# Ikea_Environmental_Sensor-Module.net
KiCad netlist of a schematic drawn in Altium Designer
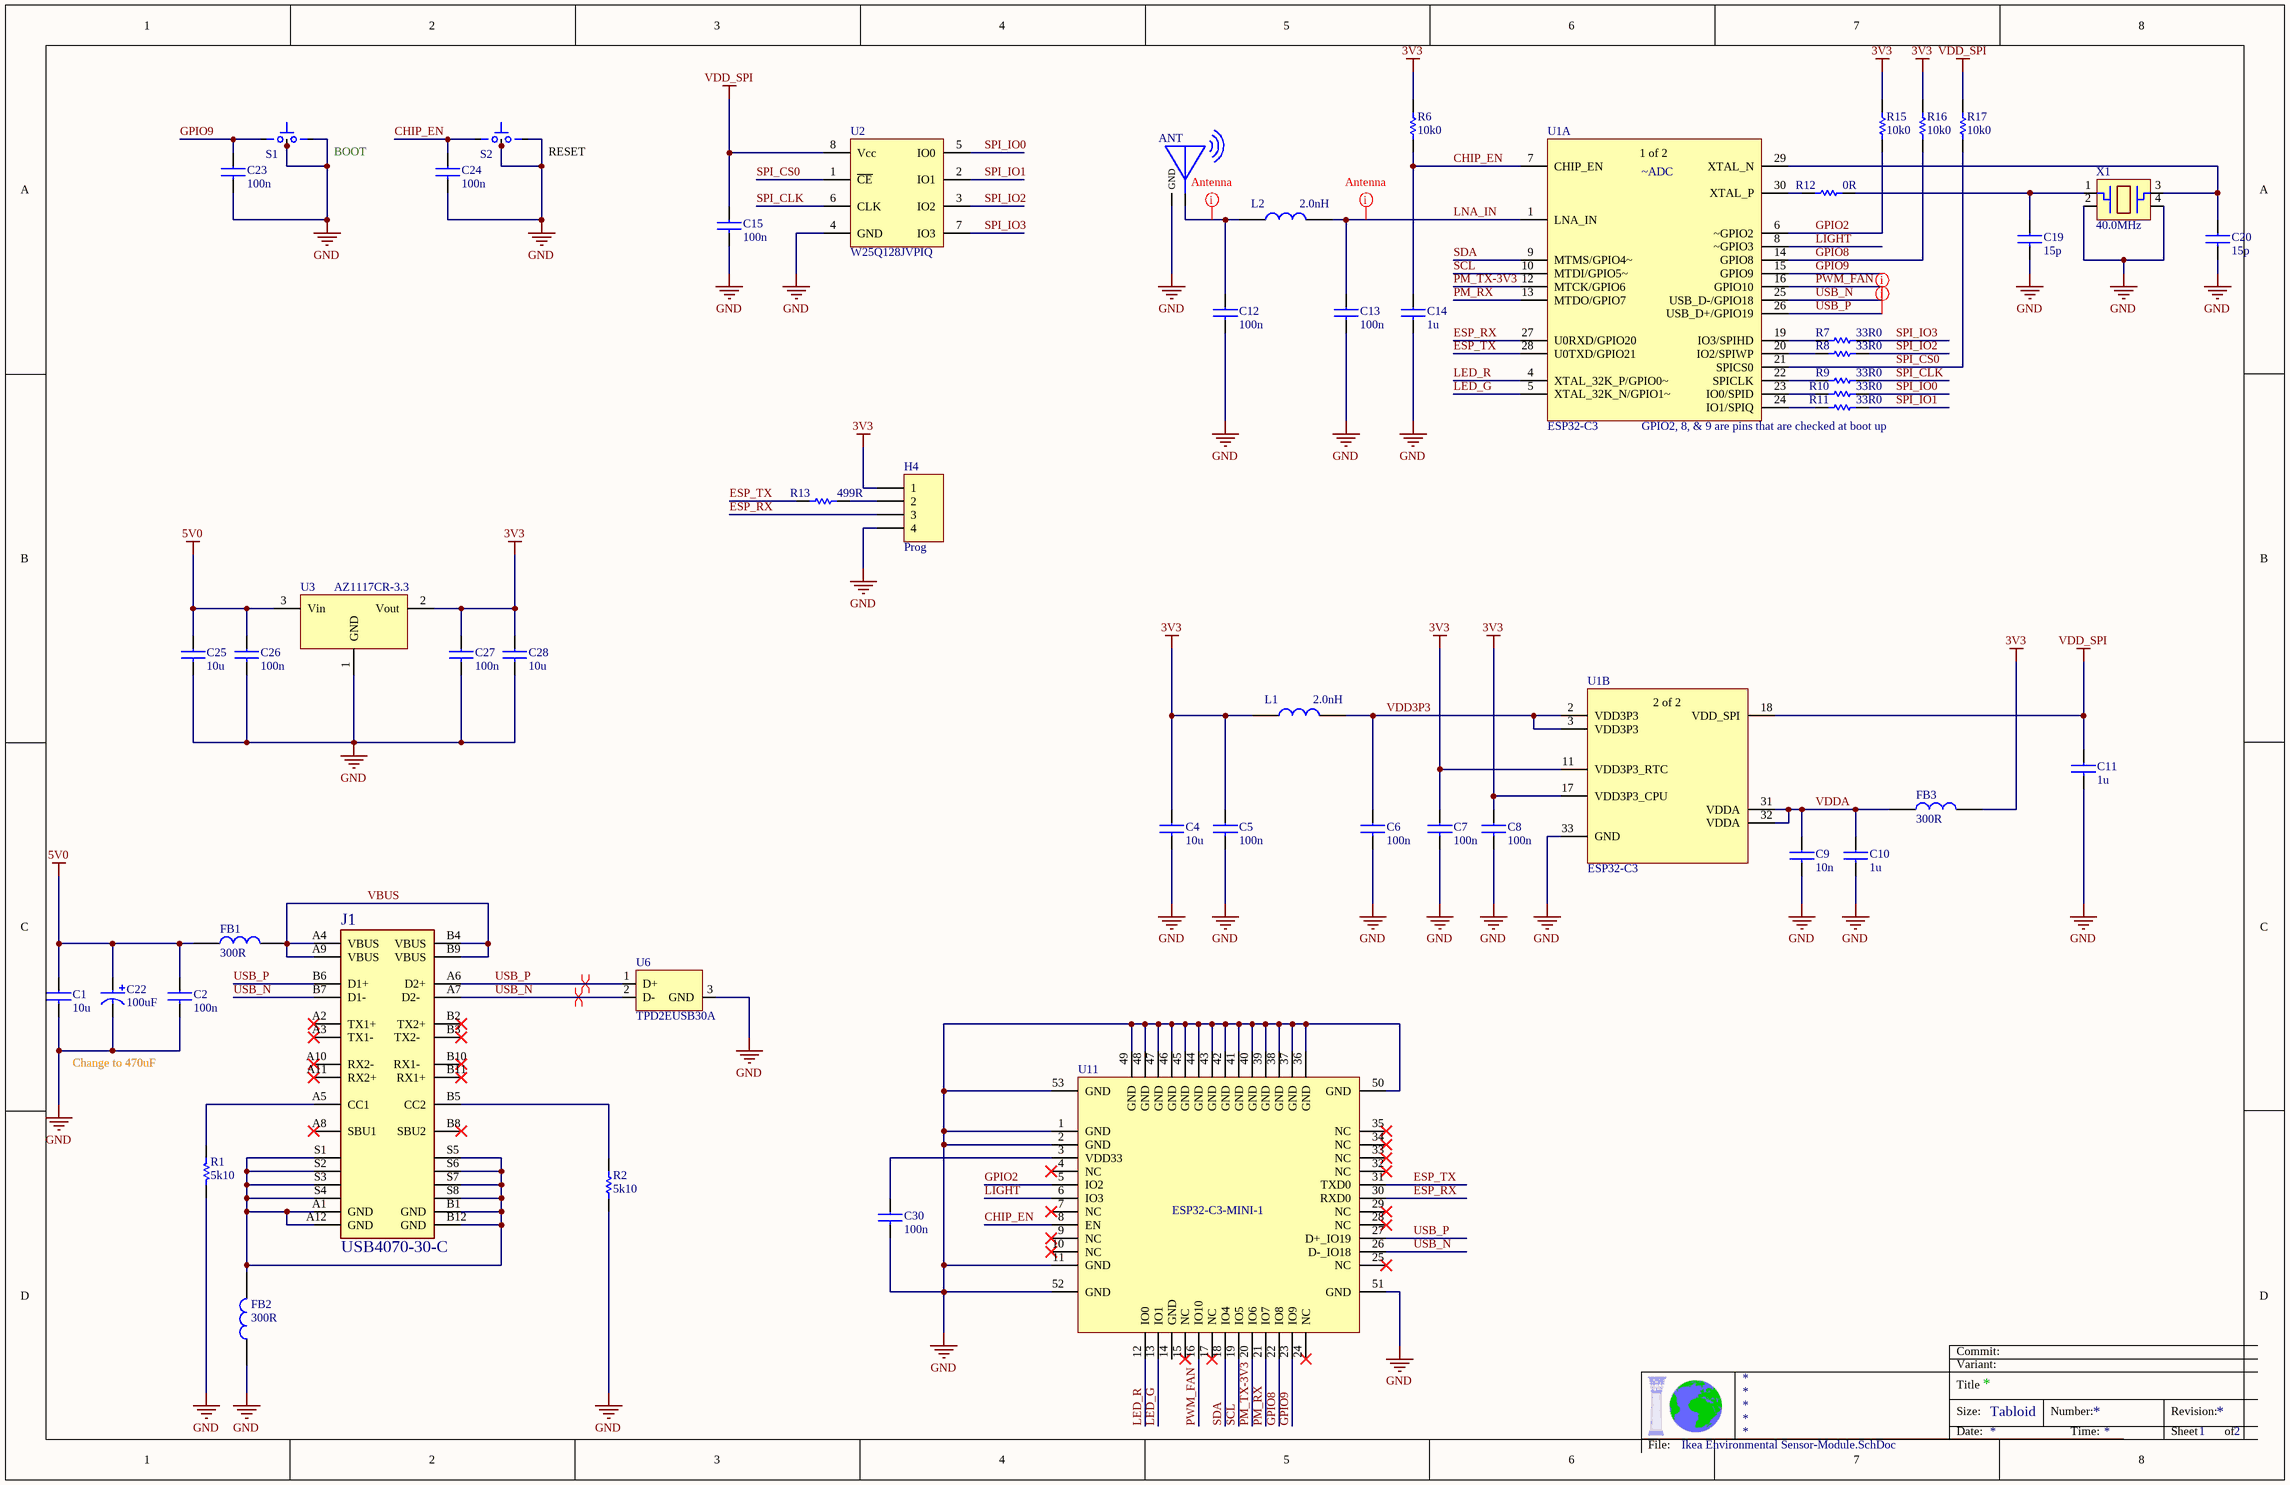
[diagram p0: Ikea Environmental Sensor-Module.SchDoc]

(export (version "E")
  (design (tool "Eeschema 10.0.6"))
  (components
    (comp (ref "ANT")
      (value "PCB Antenna")
      (footprint "MINI-ANT-TYPED-H - Flipped")
      (description "Antenna MIFA 2.4Gig")
      (fields (field (name "MANUFACTURER") "Rainsun") (field (name "LCSC_PART_NUMBER") "C99665"))
      (libsource (lib "GLIB") (part "Antenna_PCB_MIFA"))
    )
    (comp (ref "C1")
      (value "10u")
      (footprint "0603X90")
      (description "Cap, Chip, 10uF, 10V, ± 15%, X5R, 0603")
      (fields (field (name "MANUFACTURER") "NIC") (field (name "JLCPCB_PART_#") "C96446"))
      (libsource (lib "GLIB") (part "C_10u_10V_10_0603_NIC"))
    )
    (comp (ref "C2")
      (value "100n")
      (footprint "C_0402_N")
      (description "Cap, Chip, 100nF, 16V, +/-10%, X7R, 0402")
      (fields (field (name "MANUFACTURER") "NIC") (field (name "JLCPCB_PART_#") "C307331"))
      (libsource (lib "GLIB") (part "C_100n_16V_10_0402_NIC"))
    )
    (comp (ref "C4")
      (value "10u")
      (footprint "0603X90")
      (description "Cap, Chip, 10uF, 10V, ± 15%, X5R, 0603")
      (fields (field (name "MANUFACTURER") "NIC"))
      (libsource (lib "GLIB") (part "C_10u_10V_10_0603_NIC"))
    )
    (comp (ref "C5")
      (value "100n")
      (footprint "C_0402_N")
      (description "Cap, Chip, 100nF, 16V, +/-10%, X7R, 0402")
      (fields (field (name "MANUFACTURER") "NIC"))
      (libsource (lib "GLIB") (part "C_100n_16V_10_0402_NIC"))
    )
    (comp (ref "C6")
      (value "100n")
      (footprint "C_0402_N")
      (description "Cap, Chip, 100nF, 16V, +/-10%, X7R, 0402")
      (fields (field (name "MANUFACTURER") "NIC"))
      (libsource (lib "GLIB") (part "C_100n_16V_10_0402_NIC"))
    )
    (comp (ref "C7")
      (value "100n")
      (footprint "C_0402_N")
      (description "Cap, Chip, 100nF, 16V, +/-10%, X7R, 0402")
      (fields (field (name "MANUFACTURER") "NIC"))
      (libsource (lib "GLIB") (part "C_100n_16V_10_0402_NIC"))
    )
    (comp (ref "C8")
      (value "100n")
      (footprint "C_0402_N")
      (description "Cap, Chip, 100nF, 16V, +/-10%, X7R, 0402")
      (fields (field (name "MANUFACTURER") "NIC"))
      (libsource (lib "GLIB") (part "C_100n_16V_10_0402_NIC"))
    )
    (comp (ref "C9")
      (value "10n")
      (footprint "C_0402_N")
      (description "Cap, Chip, 0.01uF, 25V, 20%, X7R, 0402")
      (fields (field (name "MANUFACTURER") "NIC"))
      (libsource (lib "GLIB") (part "C_10n_25V_20_0402_NIC"))
    )
    (comp (ref "C10")
      (value "1u")
      (footprint "C_0402_N")
      (description "Cap, Chip, 1uF, 10V, 10%, X5R, 0402")
      (fields (field (name "MANUFACTURER") "NIC"))
      (libsource (lib "GLIB") (part "C_1u_10V_10_0402_NIC"))
    )
    (comp (ref "C11")
      (value "1u")
      (footprint "C_0402_N")
      (description "Cap, Chip, 1uF, 10V, 10%, X5R, 0402")
      (fields (field (name "MANUFACTURER") "NIC"))
      (libsource (lib "GLIB") (part "C_1u_10V_10_0402_NIC"))
    )
    (comp (ref "C12")
      (value "100n")
      (footprint "C_0201")
      (description "Cap, Chip, 100nF, 25V, +/-10%, X5R, 0201")
      (fields (field (name "MANUFACTURER") "Murata"))
      (libsource (lib "GLIB") (part "C_100n_25V_10_0201_Murata"))
    )
    (comp (ref "C13")
      (value "100n")
      (footprint "C_0201")
      (description "Cap, Chip, 100nF, 25V, +/-10%, X5R, 0201")
      (fields (field (name "MANUFACTURER") "Murata"))
      (libsource (lib "GLIB") (part "C_100n_25V_10_0201_Murata"))
    )
    (comp (ref "C14")
      (value "1u")
      (footprint "C_0402_N")
      (description "Cap, Chip, 1uF, 10V, 10%, X5R, 0402")
      (fields (field (name "MANUFACTURER") "NIC"))
      (libsource (lib "GLIB") (part "C_1u_10V_10_0402_NIC"))
    )
    (comp (ref "C15")
      (value "100n")
      (footprint "C_0402_N")
      (description "Cap, Chip, 100nF, 16V, +/-10%, X7R, 0402")
      (fields (field (name "MANUFACTURER") "NIC"))
      (libsource (lib "GLIB") (part "C_100n_16V_10_0402_NIC"))
    )
    (comp (ref "C19")
      (value "15p")
      (footprint "C_0402_N")
      (description "Cap, Chip, 15pF, 25V, 10%, NPO 0402")
      (fields (field (name "MANUFACTURER") "NIC"))
      (libsource (lib "GLIB") (part "C_15p_25V_10_0402_NIC"))
    )
    (comp (ref "C20")
      (value "15p")
      (footprint "C_0402_N")
      (description "Cap, Chip, 15pF, 25V, 10%, NPO 0402")
      (fields (field (name "MANUFACTURER") "NIC"))
      (libsource (lib "GLIB") (part "C_15p_25V_10_0402_NIC"))
    )
    (comp (ref "C22")
      (value "100uF")
      (footprint "CAP_6.6x6.6")
      (description "Cap AlEl, 100uF, 35V, 20%, 6.6mm dia.")
      (fields (field (name "MANUFACTURER") "Panasonic") (field (name "Comment") "100uF, 35V"))
      (libsource (lib "GLIB") (part "C_100uF_35V_20_6.6mm_Panasonic"))
    )
    (comp (ref "C23")
      (value "100n")
      (footprint "C_0402_N")
      (description "Cap, Chip, 100nF, 16V, +/-10%, X7R, 0402")
      (fields (field (name "MANUFACTURER") "NIC"))
      (libsource (lib "GLIB") (part "C_100n_16V_10_0402_NIC"))
    )
    (comp (ref "C24")
      (value "100n")
      (footprint "C_0402_N")
      (description "Cap, Chip, 100nF, 16V, +/-10%, X7R, 0402")
      (fields (field (name "MANUFACTURER") "NIC"))
      (libsource (lib "GLIB") (part "C_100n_16V_10_0402_NIC"))
    )
    (comp (ref "C25")
      (value "10u")
      (footprint "0603X90")
      (description "Cap, Chip, 10uF, 10V, ± 15%, X5R, 0603")
      (fields (field (name "MANUFACTURER") "NIC"))
      (libsource (lib "GLIB") (part "C_10u_10V_10_0603_NIC"))
    )
    (comp (ref "C26")
      (value "100n")
      (footprint "C_0402_N")
      (description "Cap, Chip, 100nF, 16V, +/-10%, X7R, 0402")
      (fields (field (name "MANUFACTURER") "NIC"))
      (libsource (lib "GLIB") (part "C_100n_16V_10_0402_NIC"))
    )
    (comp (ref "C27")
      (value "100n")
      (footprint "C_0402_N")
      (description "Cap, Chip, 100nF, 16V, +/-10%, X7R, 0402")
      (fields (field (name "MANUFACTURER") "NIC"))
      (libsource (lib "GLIB") (part "C_100n_16V_10_0402_NIC"))
    )
    (comp (ref "C28")
      (value "10u")
      (footprint "0603X90")
      (description "Cap, Chip, 10uF, 10V, ± 15%, X5R, 0603")
      (fields (field (name "MANUFACTURER") "NIC"))
      (libsource (lib "GLIB") (part "C_10u_10V_10_0603_NIC"))
    )
    (comp (ref "C30")
      (value "100n")
      (footprint "C_0402_N")
      (description "Cap, Chip, 100nF, 16V, +/-10%, X7R, 0402")
      (fields (field (name "MANUFACTURER") "NIC"))
      (libsource (lib "GLIB") (part "C_100n_16V_10_0402_NIC"))
    )
    (comp (ref "FB1")
      (value "300R")
      (footprint "FB_0402-NIC")
      (description "Ferrite bead,300 ohm@100MHz,0.15 ohm @DC, 1A, 0402")
      (fields (field (name "MANUFACTURER") "NIC"))
      (libsource (lib "GLIB") (part "FB_300R_0402_NIC"))
    )
    (comp (ref "FB2")
      (value "300R")
      (footprint "FB_0402-NIC")
      (description "Ferrite bead,300 ohm@100MHz,0.15 ohm @DC, 1A, 0402")
      (fields (field (name "MANUFACTURER") "NIC"))
      (libsource (lib "GLIB") (part "FB_300R_0402_NIC"))
    )
    (comp (ref "FB3")
      (value "300R")
      (footprint "FB_0402-NIC")
      (description "Ferrite bead,300 ohm@100MHz,0.15 ohm @DC, 1A, 0402")
      (fields (field (name "MANUFACTURER") "NIC"))
      (libsource (lib "GLIB") (part "FB_300R_0402_NIC"))
    )
    (comp (ref "H4")
      (value "Prog")
      (footprint "HDR1X4")
      (description "Header, 4-Pin")
      (libsource (lib "GLIB") (part "Header 4"))
    )
    (comp (ref "J1")
      (value "USB4070-30-C")
      (footprint "USB_C_GCT_USB4070-30-C_REVC5")
      (description "CONN RCPT USB 3.1 Type C Vertical SMT")
      (fields (field (name "MANUFACTURER") "GCT") (field (name "JLCPCB PART #") "C168703"))
      (libsource (lib "GLIB") (part "J_USB_C_REC_SMT_V"))
    )
    (comp (ref "L1")
      (value "2.0nH")
      (footprint "FB_0402-NIC")
      (description "Inductor 2.0nH, +/-0.3nH, LQG15HS2N0S02D, 0402")
      (fields (field (name "MANUFACTURER") "Murata") (field (name "JLCPCB PART #") "C880712"))
      (libsource (lib "GLIB") (part "L_2nH_LQG15HS2N0S02D_0402"))
    )
    (comp (ref "L2")
      (value "2.0nH")
      (footprint "L_0201")
      (description "Inductor 2.0nH, +/-0.1nH, 600mA, 0201")
      (fields (field (name "MANUFACTURER") "Murata"))
      (libsource (lib "GLIB") (part "L_2nH_LQP03TN2N0B02D_0201"))
    )
    (comp (ref "R1")
      (value "5k10")
      (footprint "R_0402-N")
      (description "Resistor, 5.10 kΩ, 1%, 0.06W, 0402")
      (fields (field (name "MANUFACTURER") "NIC") (field (name "JLCPCB_PART_#") "C25905"))
      (libsource (lib "GLIB") (part "R_5k10_60mW_1_0402_NIC"))
    )
    (comp (ref "R2")
      (value "5k10")
      (footprint "R_0402-N")
      (description "Resistor, 5.10 kΩ, 1%, 0.06W, 0402")
      (fields (field (name "MANUFACTURER") "NIC") (field (name "JLCPCB_PART_#") "C25905"))
      (libsource (lib "GLIB") (part "R_5k10_60mW_1_0402_NIC"))
    )
    (comp (ref "R6")
      (value "10k0")
      (footprint "R_0402-N")
      (description "Resistor, 10.0 kΩ, 1%, 0.06W, 0402")
      (fields (field (name "MANUFACTURER") "NIC"))
      (libsource (lib "GLIB") (part "R_10k0_60mW_1_0402_NIC"))
    )
    (comp (ref "R7")
      (value "33R0")
      (footprint "R_0402-N")
      (description "Resistor, 33.0 Ω, 1%, 0.06W, 0402")
      (fields (field (name "MANUFACTURER") "NIC"))
      (libsource (lib "GLIB") (part "R_33R0_60mW_1_0402_NIC"))
    )
    (comp (ref "R8")
      (value "33R0")
      (footprint "R_0402-N")
      (description "Resistor, 33.0 Ω, 1%, 0.06W, 0402")
      (fields (field (name "MANUFACTURER") "NIC"))
      (libsource (lib "GLIB") (part "R_33R0_60mW_1_0402_NIC"))
    )
    (comp (ref "R9")
      (value "33R0")
      (footprint "R_0402-N")
      (description "Resistor, 33.0 Ω, 1%, 0.06W, 0402")
      (fields (field (name "MANUFACTURER") "NIC"))
      (libsource (lib "GLIB") (part "R_33R0_60mW_1_0402_NIC"))
    )
    (comp (ref "R10")
      (value "33R0")
      (footprint "R_0402-N")
      (description "Resistor, 33.0 Ω, 1%, 0.06W, 0402")
      (fields (field (name "MANUFACTURER") "NIC"))
      (libsource (lib "GLIB") (part "R_33R0_60mW_1_0402_NIC"))
    )
    (comp (ref "R11")
      (value "33R0")
      (footprint "R_0402-N")
      (description "Resistor, 33.0 Ω, 1%, 0.06W, 0402")
      (fields (field (name "MANUFACTURER") "NIC"))
      (libsource (lib "GLIB") (part "R_33R0_60mW_1_0402_NIC"))
    )
    (comp (ref "R12")
      (value "0R")
      (footprint "R_0402-N")
      (description "Resistor, 0 Ω, 1%, 0.06W, 0402")
      (fields (field (name "MANUFACTURER") "NIC"))
      (libsource (lib "GLIB") (part "R_0R00_60mW_1_0402_NIC"))
    )
    (comp (ref "R13")
      (value "499R")
      (footprint "R_0402-N")
      (description "Resistor, 499 Ω, 1%, 0.06W, 0402")
      (fields (field (name "MANUFACTURER") "NIC"))
      (libsource (lib "GLIB") (part "R_499R_60mW_1_0402_NIC"))
    )
    (comp (ref "R15")
      (value "10k0")
      (footprint "R_0402-N")
      (description "Resistor, 10.0 kΩ, 1%, 0.06W, 0402")
      (fields (field (name "MANUFACTURER") "NIC"))
      (libsource (lib "GLIB") (part "R_10k0_60mW_1_0402_NIC"))
    )
    (comp (ref "R16")
      (value "10k0")
      (footprint "R_0402-N")
      (description "Resistor, 10.0 kΩ, 1%, 0.06W, 0402")
      (fields (field (name "MANUFACTURER") "NIC"))
      (libsource (lib "GLIB") (part "R_10k0_60mW_1_0402_NIC"))
    )
    (comp (ref "R17")
      (value "10k0")
      (footprint "R_0402-N")
      (description "Resistor, 10.0 kΩ, 1%, 0.06W, 0402")
      (fields (field (name "MANUFACTURER") "NIC"))
      (libsource (lib "GLIB") (part "R_10k0_60mW_1_0402_NIC"))
    )
    (comp (ref "S1")
      (value "BOOT")
      (footprint "SW_122514")
      (description "Side Actuated Button R/A")
      (fields (field (name "MANUFACTURER") "HYP") (field (name "JLCPCB PART #") "C319377"))
      (libsource (lib "GLIB") (part "SW_Side Actuated Button R/A"))
    )
    (comp (ref "S2")
      (value "RESET")
      (footprint "SW_122514")
      (description "Side Actuated Button R/A")
      (fields (field (name "MANUFACTURER") "HYP") (field (name "JLCPCB PART #") "C319377"))
      (libsource (lib "GLIB") (part "SW_Side Actuated Button R/A"))
    )
    (comp (ref "U1")
      (value "ESP32-C3")
      (footprint "QFN-32_5x5")
      (description "IC, ESP32-C3, 160MHz RISC-V Single Core, QFN32")
      (fields (field (name "MANUFACTURER") "Espressif Systems"))
      (libsource (lib "GLIB") (part "U_ESP32-C3_QFN32"))
    )
    (comp (ref "U2")
      (value "W25Q128JVPIQ")
      (footprint "WSON_8")
      (description "IC, Flash Memory 128Mb (16Mkx8), 3.3V, WSON8-5x6")
      (fields (field (name "MANUFACTURER") "Winbond") (field (name "JLCPCB PART #") "C2803379"))
      (libsource (lib "GLIB") (part "U_W25Q128JVPIQ_WSON8"))
    )
    (comp (ref "U3")
      (value "AZ1117CR-3.3")
      (footprint "SOT89-150P410X160-3N")
      (description "IC, CONV DC/DC LDO 3.3V, 15V In 1A, SOT89-3")
      (fields (field (name "MANUFACTURER") "Diodes Inc") (field (name "JLCPCB PART #") "C347256"))
      (libsource (lib "GLIB") (part "U_AZ1117CR-3.3TRG1_SOT89-3"))
    )
    (comp (ref "U6")
      (value "TPD2EUSB30A")
      (footprint "DRT3")
      (description "2 Channel ESD for USB 3.0")
      (fields (field (name "MANUFACTURER") "Texas Instruments") (field (name "JLCPCB_PART_#") "C94934"))
      (libsource (lib "GLIB") (part "U_TPD2EUSB30A-SOT_DRT-3"))
    )
    (comp (ref "U11")
      (value "ESP32-C3-MINI-1")
      (footprint "ESP32-C3-MINI-1")
      (description "IC, ESP32-C3-MINI-1 Module")
      (fields (field (name "MANUFACTURER") "Espressif") (field (name "JLCPCB PART #") "C2838502"))
      (libsource (lib "GLIB") (part "U_ESP32-C3-MINI-1"))
    )
    (comp (ref "X1")
      (value "40.0MHz")
      (description "X-tal, 40.000MHz, Cl=4pF, +-10ppm, 3.2x2.5")
      (fields (field (name "MANUFACTURER") "ABRACON Co") (field (name "JLCPCB PART #") "C90924"))
      (libsource (lib "GLIB") (part "X_40.000MHZ_12pF_3225"))
    )
  )
  (nets
    (net (code "1") (name "/CHIP_EN") (class "Default")
      (node (ref "C14") (pin "1") (pinfunction "1_1") (pintype "passive"))
      (node (ref "C24") (pin "1") (pinfunction "1_1") (pintype "passive"))
      (node (ref "R6") (pin "1") (pinfunction "1_1") (pintype "passive"))
      (node (ref "S2") (pin "1") (pinfunction "A_1") (pintype "passive"))
      (node (ref "U1") (pin "7") (pinfunction "CHIP_EN_7") (pintype "passive"))
      (node (ref "U11") (pin "8") (pinfunction "EN_8") (pintype "passive"))
    )
    (net (code "2") (name "/ESP_RX") (class "Default")
      (node (ref "H4") (pin "3") (pinfunction "3_3") (pintype "passive"))
      (node (ref "U1") (pin "27") (pinfunction "U0RXD/GPIO20_27") (pintype "passive"))
      (node (ref "U11") (pin "30") (pinfunction "RXD0_30") (pintype "passive"))
    )
    (net (code "3") (name "/ESP_TX") (class "Default")
      (node (ref "R13") (pin "1") (pinfunction "1_1") (pintype "passive"))
      (node (ref "U1") (pin "28") (pinfunction "U0TXD/GPIO21_28") (pintype "passive"))
      (node (ref "U11") (pin "31") (pinfunction "TXD0_31") (pintype "passive"))
    )
    (net (code "4") (name "/GPIO2") (class "Default")
      (node (ref "R15") (pin "1") (pinfunction "1_1") (pintype "passive"))
      (node (ref "U1") (pin "6") (pinfunction "~GPIO2_6") (pintype "passive"))
      (node (ref "U11") (pin "5") (pinfunction "IO2_5") (pintype "passive"))
    )
    (net (code "5") (name "/GPIO8") (class "Default")
      (node (ref "R16") (pin "1") (pinfunction "1_1") (pintype "passive"))
      (node (ref "U1") (pin "14") (pinfunction "GPIO8_14") (pintype "passive"))
      (node (ref "U11") (pin "22") (pinfunction "IO8_22") (pintype "passive"))
    )
    (net (code "6") (name "/GPIO9") (class "Default")
      (node (ref "C23") (pin "1") (pinfunction "1_1") (pintype "passive"))
      (node (ref "S1") (pin "1") (pinfunction "A_1") (pintype "passive"))
      (node (ref "U1") (pin "15") (pinfunction "GPIO9_15") (pintype "passive"))
      (node (ref "U11") (pin "23") (pinfunction "IO9_23") (pintype "passive"))
    )
    (net (code "7") (name "/LED_G") (class "Default")
      (node (ref "U1") (pin "5") (pinfunction "XTAL_32K_N/GPIO1~_5") (pintype "passive"))
      (node (ref "U11") (pin "13") (pinfunction "IO1_13") (pintype "passive"))
    )
    (net (code "8") (name "/LED_R") (class "Default")
      (node (ref "U1") (pin "4") (pinfunction "XTAL_32K_P/GPIO0~_4") (pintype "passive"))
      (node (ref "U11") (pin "12") (pinfunction "IO0_12") (pintype "passive"))
    )
    (net (code "9") (name "/LIGHT") (class "Default")
      (node (ref "U1") (pin "8") (pinfunction "~GPIO3_8") (pintype "passive"))
      (node (ref "U11") (pin "6") (pinfunction "IO3_6") (pintype "passive"))
    )
    (net (code "10") (name "/LNA_IN") (class "Default")
      (node (ref "C13") (pin "1") (pinfunction "1_1") (pintype "passive"))
      (node (ref "L2") (pin "2") (pinfunction "2_2") (pintype "passive"))
      (node (ref "U1") (pin "1") (pinfunction "LNA_IN_1") (pintype "passive"))
    )
    (net (code "11") (name "/PM_RX") (class "Default")
      (node (ref "U1") (pin "13") (pinfunction "MTDO/GPIO7_13") (pintype "passive"))
      (node (ref "U11") (pin "21") (pinfunction "IO7_21") (pintype "passive"))
    )
    (net (code "12") (name "/PM_TX-3V3") (class "Default")
      (node (ref "U1") (pin "12") (pinfunction "MTCK/GPIO6_12") (pintype "passive"))
      (node (ref "U11") (pin "20") (pinfunction "IO6_20") (pintype "passive"))
    )
    (net (code "13") (name "/PWM_FAN") (class "Default")
      (node (ref "U1") (pin "16") (pinfunction "GPIO10_16") (pintype "passive"))
      (node (ref "U11") (pin "16") (pinfunction "IO10_16") (pintype "passive"))
    )
    (net (code "14") (name "/SCL") (class "Default")
      (node (ref "U1") (pin "10") (pinfunction "MTDI/GPIO5~_10") (pintype "passive"))
      (node (ref "U11") (pin "19") (pinfunction "IO5_19") (pintype "power_in"))
    )
    (net (code "15") (name "/SDA") (class "Default")
      (node (ref "U1") (pin "9") (pinfunction "MTMS/GPIO4~_9") (pintype "passive"))
      (node (ref "U11") (pin "18") (pinfunction "IO4_18") (pintype "passive"))
    )
    (net (code "16") (name "/SPI_CLK") (class "Default")
      (node (ref "R9") (pin "2") (pinfunction "2_2") (pintype "passive"))
      (node (ref "U2") (pin "6") (pinfunction "CLK_6") (pintype "passive"))
    )
    (net (code "17") (name "/SPI_CS0") (class "Default")
      (node (ref "R17") (pin "1") (pinfunction "1_1") (pintype "passive"))
      (node (ref "U1") (pin "21") (pinfunction "SPICS0_21") (pintype "passive"))
      (node (ref "U2") (pin "1") (pinfunction "~{CE}_1") (pintype "passive"))
    )
    (net (code "18") (name "/SPI_IO0") (class "Default")
      (node (ref "R10") (pin "2") (pinfunction "2_2") (pintype "passive"))
      (node (ref "U2") (pin "5") (pinfunction "IO0_5") (pintype "passive"))
    )
    (net (code "19") (name "/SPI_IO1") (class "Default")
      (node (ref "R11") (pin "2") (pinfunction "2_2") (pintype "passive"))
      (node (ref "U2") (pin "2") (pinfunction "IO1_2") (pintype "passive"))
    )
    (net (code "20") (name "/SPI_IO2") (class "Default")
      (node (ref "R8") (pin "2") (pinfunction "2_2") (pintype "passive"))
      (node (ref "U2") (pin "3") (pinfunction "IO2_3") (pintype "passive"))
    )
    (net (code "21") (name "/SPI_IO3") (class "Default")
      (node (ref "R7") (pin "2") (pinfunction "2_2") (pintype "passive"))
      (node (ref "U2") (pin "7") (pinfunction "IO3_7") (pintype "passive"))
    )
    (net (code "22") (name "/USB_N") (class "Default")
      (node (ref "J1") (pin "A7") (pinfunction "D2-_A7") (pintype "passive"))
      (node (ref "J1") (pin "B7") (pinfunction "D1-_B7") (pintype "passive"))
      (node (ref "U1") (pin "25") (pinfunction "USB_D-/GPIO18_25") (pintype "passive"))
      (node (ref "U11") (pin "26") (pinfunction "D-_IO18_26") (pintype "passive"))
      (node (ref "U6") (pin "2") (pinfunction "D-_2") (pintype "passive"))
    )
    (net (code "23") (name "/USB_P") (class "Default")
      (node (ref "J1") (pin "A6") (pinfunction "D2+_A6") (pintype "passive"))
      (node (ref "J1") (pin "B6") (pinfunction "D1+_B6") (pintype "passive"))
      (node (ref "U1") (pin "26") (pinfunction "USB_D+/GPIO19_26") (pintype "passive"))
      (node (ref "U11") (pin "27") (pinfunction "D+_IO19_27") (pintype "passive"))
      (node (ref "U6") (pin "1") (pinfunction "D+_1") (pintype "passive"))
    )
    (net (code "24") (name "/VBUS") (class "Default")
      (node (ref "FB1") (pin "2") (pinfunction "2_2") (pintype "passive"))
      (node (ref "J1") (pin "A4") (pinfunction "VBUS_A4") (pintype "power_in"))
      (node (ref "J1") (pin "A9") (pinfunction "VBUS_A9") (pintype "power_in"))
      (node (ref "J1") (pin "B4") (pinfunction "VBUS_B4") (pintype "power_in"))
      (node (ref "J1") (pin "B9") (pinfunction "VBUS_B9") (pintype "power_in"))
    )
    (net (code "25") (name "/VDD3P3") (class "Default")
      (node (ref "C6") (pin "1") (pinfunction "1_1") (pintype "passive"))
      (node (ref "L1") (pin "2") (pinfunction "2_2") (pintype "passive"))
      (node (ref "U1") (pin "2") (pinfunction "VDD3P3_2") (pintype "power_in"))
      (node (ref "U1") (pin "3") (pinfunction "VDD3P3_3") (pintype "power_in"))
    )
    (net (code "26") (name "/VDDA") (class "Default")
      (node (ref "C10") (pin "1") (pinfunction "1_1") (pintype "passive"))
      (node (ref "C9") (pin "1") (pinfunction "1_1") (pintype "passive"))
      (node (ref "FB3") (pin "1") (pinfunction "1_1") (pintype "passive"))
      (node (ref "U1") (pin "31") (pinfunction "VDDA_31") (pintype "power_in"))
      (node (ref "U1") (pin "32") (pinfunction "VDDA_32") (pintype "power_in"))
    )
    (net (code "27") (name "3V3") (class "Default")
      (node (ref "C27") (pin "1") (pinfunction "1_1") (pintype "passive"))
      (node (ref "C28") (pin "1") (pinfunction "1_1") (pintype "passive"))
      (node (ref "C4") (pin "1") (pinfunction "1_1") (pintype "passive"))
      (node (ref "C5") (pin "1") (pinfunction "1_1") (pintype "passive"))
      (node (ref "C7") (pin "1") (pinfunction "1_1") (pintype "passive"))
      (node (ref "C8") (pin "1") (pinfunction "1_1") (pintype "passive"))
      (node (ref "FB3") (pin "2") (pinfunction "2_2") (pintype "passive"))
      (node (ref "H4") (pin "1") (pinfunction "1_1") (pintype "passive"))
      (node (ref "L1") (pin "1") (pinfunction "1_1") (pintype "passive"))
      (node (ref "R15") (pin "2") (pinfunction "2_2") (pintype "passive"))
      (node (ref "R16") (pin "2") (pinfunction "2_2") (pintype "passive"))
      (node (ref "R6") (pin "2") (pinfunction "2_2") (pintype "passive"))
      (node (ref "U1") (pin "11") (pinfunction "VDD3P3_RTC_11") (pintype "power_in"))
      (node (ref "U1") (pin "17") (pinfunction "VDD3P3_CPU_17") (pintype "power_in"))
      (node (ref "U3") (pin "2") (pinfunction "Vout_2") (pintype "power_in"))
    )
    (net (code "28") (name "5V0") (class "Default")
      (node (ref "C1") (pin "1") (pinfunction "1_1") (pintype "passive"))
      (node (ref "C2") (pin "1") (pinfunction "1_1") (pintype "passive"))
      (node (ref "C22") (pin "1") (pinfunction "1_1") (pintype "passive"))
      (node (ref "C25") (pin "1") (pinfunction "1_1") (pintype "passive"))
      (node (ref "C26") (pin "1") (pinfunction "1_1") (pintype "passive"))
      (node (ref "FB1") (pin "1") (pinfunction "1_1") (pintype "passive"))
      (node (ref "U3") (pin "3") (pinfunction "Vin_3") (pintype "power_in"))
    )
    (net (code "29") (name "GND") (class "Default")
      (node (ref "ANT") (pin "2") (pinfunction "GND_2") (pintype "passive"))
      (node (ref "C1") (pin "2") (pinfunction "2_2") (pintype "passive"))
      (node (ref "C10") (pin "2") (pinfunction "2_2") (pintype "passive"))
      (node (ref "C11") (pin "2") (pinfunction "2_2") (pintype "passive"))
      (node (ref "C12") (pin "2") (pinfunction "2_2") (pintype "passive"))
      (node (ref "C13") (pin "2") (pinfunction "2_2") (pintype "passive"))
      (node (ref "C14") (pin "2") (pinfunction "2_2") (pintype "passive"))
      (node (ref "C15") (pin "2") (pinfunction "2_2") (pintype "passive"))
      (node (ref "C19") (pin "2") (pinfunction "2_2") (pintype "passive"))
      (node (ref "C2") (pin "2") (pinfunction "2_2") (pintype "passive"))
      (node (ref "C20") (pin "2") (pinfunction "2_2") (pintype "passive"))
      (node (ref "C22") (pin "2") (pinfunction "2_2") (pintype "passive"))
      (node (ref "C23") (pin "2") (pinfunction "2_2") (pintype "passive"))
      (node (ref "C24") (pin "2") (pinfunction "2_2") (pintype "passive"))
      (node (ref "C25") (pin "2") (pinfunction "2_2") (pintype "passive"))
      (node (ref "C26") (pin "2") (pinfunction "2_2") (pintype "passive"))
      (node (ref "C27") (pin "2") (pinfunction "2_2") (pintype "passive"))
      (node (ref "C28") (pin "2") (pinfunction "2_2") (pintype "passive"))
      (node (ref "C30") (pin "2") (pinfunction "2_2") (pintype "passive"))
      (node (ref "C4") (pin "2") (pinfunction "2_2") (pintype "passive"))
      (node (ref "C5") (pin "2") (pinfunction "2_2") (pintype "passive"))
      (node (ref "C6") (pin "2") (pinfunction "2_2") (pintype "passive"))
      (node (ref "C7") (pin "2") (pinfunction "2_2") (pintype "passive"))
      (node (ref "C8") (pin "2") (pinfunction "2_2") (pintype "passive"))
      (node (ref "C9") (pin "2") (pinfunction "2_2") (pintype "passive"))
      (node (ref "FB2") (pin "1") (pinfunction "1_1") (pintype "passive"))
      (node (ref "H4") (pin "4") (pinfunction "4_4") (pintype "passive"))
      (node (ref "R1") (pin "1") (pinfunction "1_1") (pintype "passive"))
      (node (ref "R2") (pin "1") (pinfunction "1_1") (pintype "passive"))
      (node (ref "S1") (pin "2") (pinfunction "B_2") (pintype "passive"))
      (node (ref "S1") (pin "3") (pinfunction "3_3") (pintype "passive"))
      (node (ref "S1") (pin "4") (pinfunction "4_4") (pintype "passive"))
      (node (ref "S2") (pin "2") (pinfunction "B_2") (pintype "passive"))
      (node (ref "S2") (pin "3") (pinfunction "3_3") (pintype "passive"))
      (node (ref "S2") (pin "4") (pinfunction "4_4") (pintype "passive"))
      (node (ref "U1") (pin "33") (pinfunction "GND_33") (pintype "power_in"))
      (node (ref "U11") (pin "1") (pinfunction "GND_1") (pintype "power_in"))
      (node (ref "U11") (pin "11") (pinfunction "GND_11") (pintype "passive"))
      (node (ref "U11") (pin "2") (pinfunction "GND_2") (pintype "power_in"))
      (node (ref "U11") (pin "36") (pinfunction "GND_36") (pintype "power_in"))
      (node (ref "U11") (pin "37") (pinfunction "GND_37") (pintype "power_in"))
      (node (ref "U11") (pin "38") (pinfunction "GND_38") (pintype "power_in"))
      (node (ref "U11") (pin "39") (pinfunction "GND_39") (pintype "power_in"))
      (node (ref "U11") (pin "40") (pinfunction "GND_40") (pintype "power_in"))
      (node (ref "U11") (pin "41") (pinfunction "GND_41") (pintype "power_in"))
      (node (ref "U11") (pin "42") (pinfunction "GND_42") (pintype "power_in"))
      (node (ref "U11") (pin "43") (pinfunction "GND_43") (pintype "power_in"))
      (node (ref "U11") (pin "44") (pinfunction "GND_44") (pintype "power_in"))
      (node (ref "U11") (pin "45") (pinfunction "GND_45") (pintype "power_in"))
      (node (ref "U11") (pin "46") (pinfunction "GND_46") (pintype "power_in"))
      (node (ref "U11") (pin "47") (pinfunction "GND_47") (pintype "power_in"))
      (node (ref "U11") (pin "48") (pinfunction "GND_48") (pintype "power_in"))
      (node (ref "U11") (pin "49") (pinfunction "GND_49") (pintype "power_in"))
      (node (ref "U11") (pin "50") (pinfunction "GND_50") (pintype "power_in"))
      (node (ref "U11") (pin "51") (pinfunction "GND_51") (pintype "power_in"))
      (node (ref "U11") (pin "52") (pinfunction "GND_52") (pintype "power_in"))
      (node (ref "U11") (pin "53") (pinfunction "GND_53") (pintype "power_in"))
      (node (ref "U2") (pin "4") (pinfunction "GND_4") (pintype "power_in"))
      (node (ref "U3") (pin "1") (pinfunction "GND_1") (pintype "power_in"))
      (node (ref "U6") (pin "3") (pinfunction "GND_3") (pintype "power_in"))
      (node (ref "X1") (pin "2") (pinfunction "GND_2") (pintype "passive"))
      (node (ref "X1") (pin "4") (pinfunction "GND_4") (pintype "passive"))
    )
    (net (code "30") (name "Net-(ANT-Pad1)") (class "Default")
      (node (ref "ANT") (pin "1") (pintype "passive"))
      (node (ref "C12") (pin "1") (pinfunction "1_1") (pintype "passive"))
      (node (ref "L2") (pin "1") (pinfunction "1_1") (pintype "passive"))
    )
    (net (code "31") (name "Net-(C19-Pad1)") (class "Default")
      (node (ref "C19") (pin "1") (pinfunction "1_1") (pintype "passive"))
      (node (ref "R12") (pin "2") (pinfunction "2_2") (pintype "passive"))
      (node (ref "X1") (pin "1") (pinfunction "1_1") (pintype "passive"))
    )
    (net (code "32") (name "Net-(FB2-Pad2)") (class "Default")
      (node (ref "FB2") (pin "2") (pinfunction "2_2") (pintype "passive"))
      (node (ref "J1") (pin "A1") (pinfunction "GND_A1") (pintype "power_in"))
      (node (ref "J1") (pin "A12") (pinfunction "GND_A12") (pintype "power_in"))
      (node (ref "J1") (pin "B1") (pinfunction "GND_B1") (pintype "power_in"))
      (node (ref "J1") (pin "B12") (pinfunction "GND_B12") (pintype "power_in"))
      (node (ref "J1") (pin "S1") (pinfunction "Shield_S1") (pintype "passive"))
      (node (ref "J1") (pin "S2") (pinfunction "Shield_S2") (pintype "passive"))
      (node (ref "J1") (pin "S3") (pinfunction "Shield_S3") (pintype "passive"))
      (node (ref "J1") (pin "S4") (pinfunction "Shield_S4") (pintype "passive"))
      (node (ref "J1") (pin "S5") (pinfunction "Shield_S5") (pintype "passive"))
      (node (ref "J1") (pin "S6") (pinfunction "Shield_S6") (pintype "passive"))
      (node (ref "J1") (pin "S7") (pinfunction "Shield_S7") (pintype "passive"))
      (node (ref "J1") (pin "S8") (pinfunction "Shield_S8") (pintype "passive"))
    )
    (net (code "33") (name "Net-(H4-Pad2)") (class "Default")
      (node (ref "H4") (pin "2") (pinfunction "2_2") (pintype "passive"))
      (node (ref "R13") (pin "2") (pinfunction "2_2") (pintype "passive"))
    )
    (net (code "34") (name "Net-(J1-CC1)") (class "Default")
      (node (ref "J1") (pin "A5") (pinfunction "CC1_A5") (pintype "passive"))
      (node (ref "R1") (pin "2") (pinfunction "2_2") (pintype "passive"))
    )
    (net (code "35") (name "Net-(J1-CC2)") (class "Default")
      (node (ref "J1") (pin "B5") (pinfunction "CC2_B5") (pintype "passive"))
      (node (ref "R2") (pin "2") (pinfunction "2_2") (pintype "passive"))
    )
    (net (code "36") (name "Net-(U1A-IO0{slash}SPID)") (class "Default")
      (node (ref "R10") (pin "1") (pinfunction "1_1") (pintype "passive"))
      (node (ref "U1") (pin "23") (pinfunction "IO0/SPID_23") (pintype "passive"))
    )
    (net (code "37") (name "Net-(U1A-IO1{slash}SPIQ)") (class "Default")
      (node (ref "R11") (pin "1") (pinfunction "1_1") (pintype "passive"))
      (node (ref "U1") (pin "24") (pinfunction "IO1/SPIQ_24") (pintype "passive"))
    )
    (net (code "38") (name "Net-(U1A-IO2{slash}SPIWP)") (class "Default")
      (node (ref "R8") (pin "1") (pinfunction "1_1") (pintype "passive"))
      (node (ref "U1") (pin "20") (pinfunction "IO2/SPIWP_20") (pintype "passive"))
    )
    (net (code "39") (name "Net-(U1A-IO3{slash}SPIHD)") (class "Default")
      (node (ref "R7") (pin "1") (pinfunction "1_1") (pintype "passive"))
      (node (ref "U1") (pin "19") (pinfunction "IO3/SPIHD_19") (pintype "passive"))
    )
    (net (code "40") (name "Net-(U1A-SPICLK)") (class "Default")
      (node (ref "R9") (pin "1") (pinfunction "1_1") (pintype "passive"))
      (node (ref "U1") (pin "22") (pinfunction "SPICLK_22") (pintype "passive"))
    )
    (net (code "41") (name "Net-(U1A-XTAL_N)") (class "Default")
      (node (ref "C20") (pin "1") (pinfunction "1_1") (pintype "passive"))
      (node (ref "U1") (pin "29") (pinfunction "XTAL_N_29") (pintype "passive"))
      (node (ref "X1") (pin "3") (pinfunction "3_3") (pintype "passive"))
    )
    (net (code "42") (name "Net-(U1A-XTAL_P)") (class "Default")
      (node (ref "R12") (pin "1") (pinfunction "1_1") (pintype "passive"))
      (node (ref "U1") (pin "30") (pinfunction "XTAL_P_30") (pintype "passive"))
    )
    (net (code "43") (name "Net-(U11-VDD33)") (class "Default")
      (node (ref "C30") (pin "1") (pinfunction "1_1") (pintype "passive"))
      (node (ref "U11") (pin "3") (pinfunction "VDD33_3") (pintype "power_in"))
    )
    (net (code "44") (name "VDD_SPI") (class "Default")
      (node (ref "C11") (pin "1") (pinfunction "1_1") (pintype "passive"))
      (node (ref "C15") (pin "1") (pinfunction "1_1") (pintype "passive"))
      (node (ref "R17") (pin "2") (pinfunction "2_2") (pintype "passive"))
      (node (ref "U1") (pin "18") (pinfunction "VDD_SPI_18") (pintype "power_in"))
      (node (ref "U2") (pin "8") (pinfunction "Vcc_8") (pintype "power_in"))
    )
    (net (code "45") (name "unconnected-(J1-RX1+-PadB11)") (class "Default")
      (node (ref "J1") (pin "B11") (pinfunction "RX1+_B11") (pintype "passive+no_connect"))
    )
    (net (code "46") (name "unconnected-(J1-RX1--PadB10)") (class "Default")
      (node (ref "J1") (pin "B10") (pinfunction "RX1-_B10") (pintype "passive+no_connect"))
    )
    (net (code "47") (name "unconnected-(J1-RX2+-PadA11)") (class "Default")
      (node (ref "J1") (pin "A11") (pinfunction "RX2+_A11") (pintype "passive+no_connect"))
    )
    (net (code "48") (name "unconnected-(J1-RX2--PadA10)") (class "Default")
      (node (ref "J1") (pin "A10") (pinfunction "RX2-_A10") (pintype "passive+no_connect"))
    )
    (net (code "49") (name "unconnected-(J1-SBU1-PadA8)") (class "Default")
      (node (ref "J1") (pin "A8") (pinfunction "SBU1_A8") (pintype "passive+no_connect"))
    )
    (net (code "50") (name "unconnected-(J1-SBU2-PadB8)") (class "Default")
      (node (ref "J1") (pin "B8") (pinfunction "SBU2_B8") (pintype "passive+no_connect"))
    )
    (net (code "51") (name "unconnected-(J1-TX1+-PadA2)") (class "Default")
      (node (ref "J1") (pin "A2") (pinfunction "TX1+_A2") (pintype "passive+no_connect"))
    )
    (net (code "52") (name "unconnected-(J1-TX1--PadA3)") (class "Default")
      (node (ref "J1") (pin "A3") (pinfunction "TX1-_A3") (pintype "passive+no_connect"))
    )
    (net (code "53") (name "unconnected-(J1-TX2+-PadB2)") (class "Default")
      (node (ref "J1") (pin "B2") (pinfunction "TX2+_B2") (pintype "passive+no_connect"))
    )
    (net (code "54") (name "unconnected-(J1-TX2--PadB3)") (class "Default")
      (node (ref "J1") (pin "B3") (pinfunction "TX2-_B3") (pintype "passive+no_connect"))
    )
    (net (code "55") (name "unconnected-(U11-GND-Pad14)") (class "Default")
      (node (ref "U11") (pin "14") (pinfunction "GND_14") (pintype "passive"))
    )
    (net (code "56") (name "unconnected-(U11-NC-Pad4)") (class "Default")
      (node (ref "U11") (pin "4") (pinfunction "NC_4") (pintype "passive+no_connect"))
    )
    (net (code "57") (name "unconnected-(U11-NC-Pad7)") (class "Default")
      (node (ref "U11") (pin "7") (pinfunction "NC_7") (pintype "passive+no_connect"))
    )
    (net (code "58") (name "unconnected-(U11-NC-Pad9)") (class "Default")
      (node (ref "U11") (pin "9") (pinfunction "NC_9") (pintype "passive+no_connect"))
    )
    (net (code "59") (name "unconnected-(U11-NC-Pad10)") (class "Default")
      (node (ref "U11") (pin "10") (pinfunction "NC_10") (pintype "passive+no_connect"))
    )
    (net (code "60") (name "unconnected-(U11-NC-Pad15)") (class "Default")
      (node (ref "U11") (pin "15") (pinfunction "NC_15") (pintype "passive+no_connect"))
    )
    (net (code "61") (name "unconnected-(U11-NC-Pad17)") (class "Default")
      (node (ref "U11") (pin "17") (pinfunction "NC_17") (pintype "passive+no_connect"))
    )
    (net (code "62") (name "unconnected-(U11-NC-Pad24)") (class "Default")
      (node (ref "U11") (pin "24") (pinfunction "NC_24") (pintype "passive+no_connect"))
    )
    (net (code "63") (name "unconnected-(U11-NC-Pad25)") (class "Default")
      (node (ref "U11") (pin "25") (pinfunction "NC_25") (pintype "passive+no_connect"))
    )
    (net (code "64") (name "unconnected-(U11-NC-Pad28)") (class "Default")
      (node (ref "U11") (pin "28") (pinfunction "NC_28") (pintype "passive+no_connect"))
    )
    (net (code "65") (name "unconnected-(U11-NC-Pad29)") (class "Default")
      (node (ref "U11") (pin "29") (pinfunction "NC_29") (pintype "passive+no_connect"))
    )
    (net (code "66") (name "unconnected-(U11-NC-Pad32)") (class "Default")
      (node (ref "U11") (pin "32") (pinfunction "NC_32") (pintype "passive+no_connect"))
    )
    (net (code "67") (name "unconnected-(U11-NC-Pad33)") (class "Default")
      (node (ref "U11") (pin "33") (pinfunction "NC_33") (pintype "passive+no_connect"))
    )
    (net (code "68") (name "unconnected-(U11-NC-Pad34)") (class "Default")
      (node (ref "U11") (pin "34") (pinfunction "NC_34") (pintype "passive+no_connect"))
    )
    (net (code "69") (name "unconnected-(U11-NC-Pad35)") (class "Default")
      (node (ref "U11") (pin "35") (pinfunction "NC_35") (pintype "passive+no_connect"))
    )
  )
)
